# hearingamp_PAM_v2.net
KiCad netlist of a schematic drawn in EAGLE
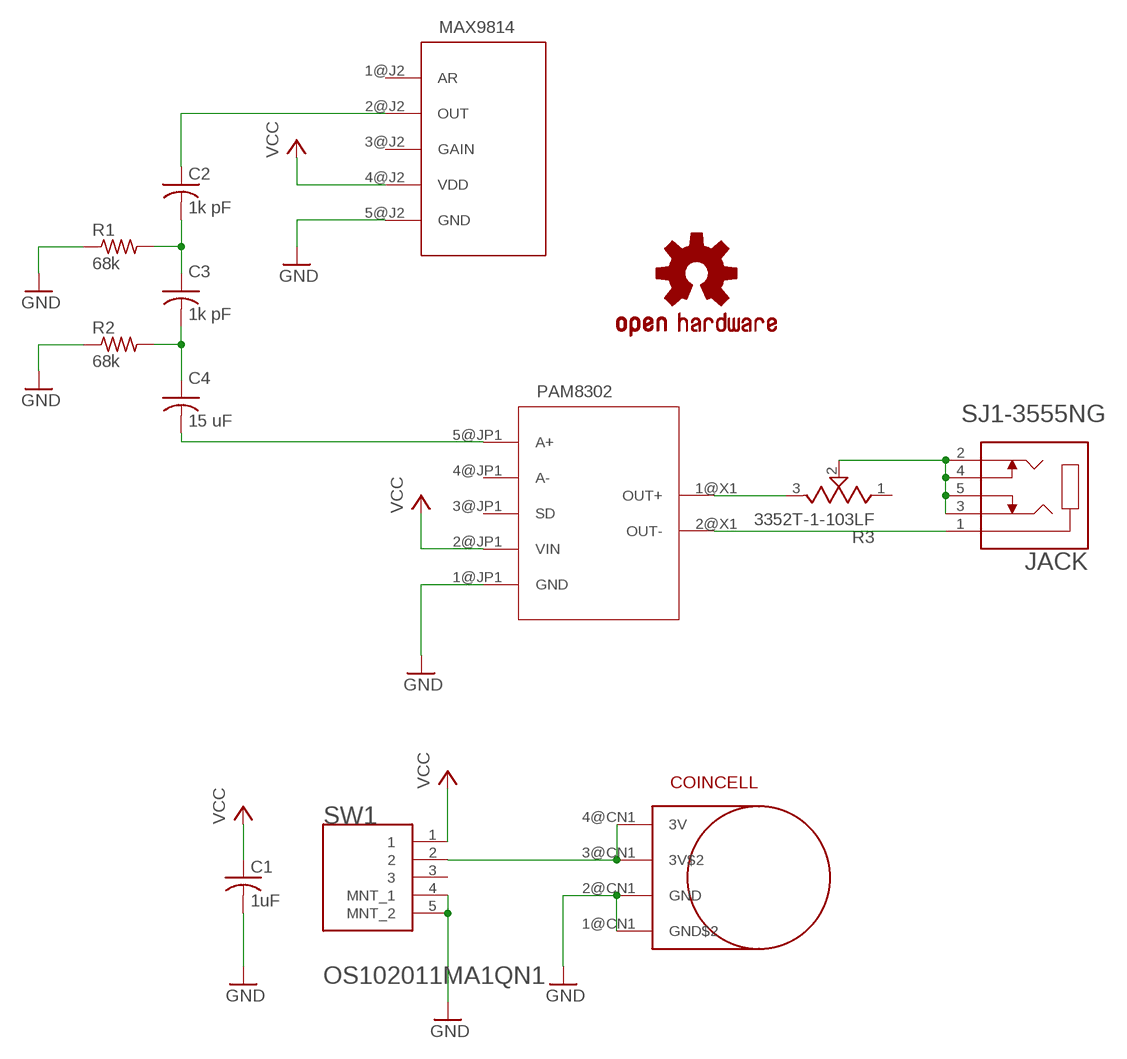
[diagram p0: schematic, sheet 1]

(export (version "E")
  (design (tool "Eeschema 10.0.6"))
  (components
    (comp (ref "C1")
      (value "1uF")
      (footprint "eagle-import:C050-025X075")
      (libsource (lib "eagle-import") (part "C-US050-025X075"))
    )
    (comp (ref "C2")
      (value "1k pF")
      (footprint "eagle-import:C050-025X075")
      (libsource (lib "eagle-import") (part "C-US050-025X075"))
    )
    (comp (ref "C3")
      (value "1k pF")
      (footprint "eagle-import:C050-025X075")
      (libsource (lib "eagle-import") (part "C-US050-025X075"))
    )
    (comp (ref "C4")
      (value "15 uF")
      (footprint "eagle-import:C050-025X075")
      (libsource (lib "eagle-import") (part "C-US050-025X075"))
    )
    (comp (ref "COINCELL")
      (value "20MMCOINCELL")
      (footprint "eagle-import:CN1_COIN20MM")
      (libsource (lib "eagle-import") (part "20MMCOINCELL"))
    )
    (comp (ref "JACK")
      (value "SJ1-3555NG")
      (footprint "eagle-import:CUI_SJ1-3555NG")
      (fields (field (name "MF") "CUI Devices"))
      (libsource (lib "eagle-import") (part "SJ1-3555NG"))
    )
    (comp (ref "LOGO1")
      (value "OSHW-LOGOL")
      (footprint "eagle-import:OSHW-LOGO-L")
      (libsource (lib "eagle-import") (part "OSHW-LOGOL"))
    )
    (comp (ref "MAX9814")
      (value "ADAFRUIT_MAX9814")
      (footprint "eagle-import:ADAFRUIT_MAX9814")
      (libsource (lib "eagle-import") (part "ADAFRUIT_MAX9814"))
    )
    (comp (ref "PAM1")
      (value "ADAFRUIT_PAM8302A")
      (footprint "eagle-import:ADAFRUIT_PAM8302")
      (libsource (lib "eagle-import") (part "ADAFRUIT_PAM8302A"))
    )
    (comp (ref "R1")
      (value "68k")
      (footprint "eagle-import:0204_7")
      (libsource (lib "eagle-import") (part "R-US_0204/7"))
    )
    (comp (ref "R2")
      (value "68k")
      (footprint "eagle-import:0204_7")
      (libsource (lib "eagle-import") (part "R-US_0204/7"))
    )
    (comp (ref "R3")
      (value "3352T-1-103LF")
      (footprint "eagle-import:TRIM_3352T-1-103LF")
      (fields (field (name "MF") "Bourns"))
      (libsource (lib "eagle-import") (part "3352T-1-103LF"))
    )
    (comp (ref "SW1")
      (value "C&K_OS102011MA1QN1C&K_OS102011MA1QN1_0_0")
      (footprint "eagle-import:C&K_OS102011MA1QN1_0")
      (fields
        (field (name "DIGIKEY_PART_NUMBER") "CKN9559-ND")
        (field (name "MF") "C&K")
        (field (name "MOUSER_PART_NUMBER") "OS102011MA1QN1")
      )
      (libsource (lib "eagle-import") (part "C&K_OS102011MA1QN1C&K_OS102011MA1QN1_0_0"))
    )
  )
  (nets
    (net (code "1") (name "GND") (class "Default")
      (node (ref "C1") (pin "2") (pinfunction "2_2") (pintype "passive"))
      (node (ref "COINCELL") (pin "1@CN1") (pinfunction "GND$2_1@CN1") (pintype "bidirectional"))
      (node (ref "COINCELL") (pin "2@CN1") (pinfunction "GND_2@CN1") (pintype "bidirectional"))
      (node (ref "MAX9814") (pin "5@J2") (pinfunction "GND_5@J2") (pintype "bidirectional"))
      (node (ref "PAM1") (pin "1@JP1") (pinfunction "GND_1@JP1") (pintype "bidirectional"))
      (node (ref "R1") (pin "1") (pinfunction "1_1") (pintype "passive"))
      (node (ref "R2") (pin "1") (pinfunction "1_1") (pintype "passive"))
      (node (ref "SW1") (pin "4") (pinfunction "MNT_1_4") (pintype "passive"))
      (node (ref "SW1") (pin "5") (pinfunction "MNT_2_5") (pintype "passive"))
    )
    (net (code "2") (name "Net-(C2-Pad2)") (class "Default")
      (node (ref "C2") (pin "2") (pinfunction "2_2") (pintype "passive"))
      (node (ref "C3") (pin "1") (pinfunction "1_1") (pintype "passive"))
      (node (ref "R1") (pin "2") (pinfunction "2_2") (pintype "passive"))
    )
    (net (code "3") (name "Net-(C3-Pad2)") (class "Default")
      (node (ref "C3") (pin "2") (pinfunction "2_2") (pintype "passive"))
      (node (ref "C4") (pin "1") (pinfunction "1_1") (pintype "passive"))
      (node (ref "R2") (pin "2") (pinfunction "2_2") (pintype "passive"))
    )
    (net (code "4") (name "Net-(COINCELL-3V$2)") (class "Default")
      (node (ref "COINCELL") (pin "3@CN1") (pinfunction "3V$2_3@CN1") (pintype "bidirectional"))
      (node (ref "COINCELL") (pin "4@CN1") (pinfunction "3V_4@CN1") (pintype "bidirectional"))
      (node (ref "SW1") (pin "2") (pinfunction "2_2") (pintype "passive"))
    )
    (net (code "5") (name "Net-(MAX9814-OUT)") (class "Default")
      (node (ref "C2") (pin "1") (pinfunction "1_1") (pintype "passive"))
      (node (ref "MAX9814") (pin "2@J2") (pinfunction "OUT_2@J2") (pintype "output"))
    )
    (net (code "6") (name "Net-(PAM1-A+)") (class "Default")
      (node (ref "C4") (pin "2") (pinfunction "2_2") (pintype "passive"))
      (node (ref "PAM1") (pin "5@JP1") (pinfunction "A+_5@JP1") (pintype "bidirectional"))
    )
    (net (code "7") (name "Net-(PAM1-OUT+)") (class "Default")
      (node (ref "PAM1") (pin "1@X1") (pinfunction "OUT+_1@X1") (pintype "bidirectional"))
      (node (ref "R3") (pin "3") (pinfunction "CW_3") (pintype "passive"))
    )
    (net (code "8") (name "Net-(PAM1-OUT-)") (class "Default")
      (node (ref "JACK") (pin "1") (pinfunction "1_1") (pintype "passive"))
      (node (ref "PAM1") (pin "2@X1") (pinfunction "OUT-_2@X1") (pintype "bidirectional"))
    )
    (net (code "9") (name "Net-(R3-WIPER)") (class "Default")
      (node (ref "JACK") (pin "2") (pinfunction "2_2") (pintype "passive"))
      (node (ref "JACK") (pin "3") (pinfunction "3_3") (pintype "passive"))
      (node (ref "JACK") (pin "4") (pinfunction "4_4") (pintype "passive"))
      (node (ref "JACK") (pin "5") (pinfunction "5_5") (pintype "passive"))
      (node (ref "R3") (pin "2") (pinfunction "WIPER_2") (pintype "passive"))
    )
    (net (code "10") (name "VCC") (class "Default")
      (node (ref "C1") (pin "1") (pinfunction "1_1") (pintype "passive"))
      (node (ref "MAX9814") (pin "4@J2") (pinfunction "VDD_4@J2") (pintype "power_in"))
      (node (ref "PAM1") (pin "2@JP1") (pinfunction "VIN_2@JP1") (pintype "bidirectional"))
      (node (ref "SW1") (pin "1") (pinfunction "1_1") (pintype "passive"))
    )
    (net (code "11") (name "unconnected-(MAX9814-AR-Pad1@J2)") (class "Default")
      (node (ref "MAX9814") (pin "1@J2") (pinfunction "AR_1@J2") (pintype "input"))
    )
    (net (code "12") (name "unconnected-(MAX9814-GAIN-Pad3@J2)") (class "Default")
      (node (ref "MAX9814") (pin "3@J2") (pinfunction "GAIN_3@J2") (pintype "bidirectional"))
    )
    (net (code "13") (name "unconnected-(PAM1-A--Pad4@JP1)") (class "Default")
      (node (ref "PAM1") (pin "4@JP1") (pinfunction "A-_4@JP1") (pintype "bidirectional"))
    )
    (net (code "14") (name "unconnected-(PAM1-SD-Pad3@JP1)") (class "Default")
      (node (ref "PAM1") (pin "3@JP1") (pinfunction "SD_3@JP1") (pintype "bidirectional"))
    )
    (net (code "15") (name "unconnected-(R3-CCW-Pad1)") (class "Default")
      (node (ref "R3") (pin "1") (pinfunction "CCW_1") (pintype "passive"))
    )
    (net (code "16") (name "unconnected-(SW1-Pad3)") (class "Default")
      (node (ref "SW1") (pin "3") (pinfunction "3_3") (pintype "passive"))
    )
  )
)
